# shift.net
KiCad netlist of a schematic drawn in Altium Designer
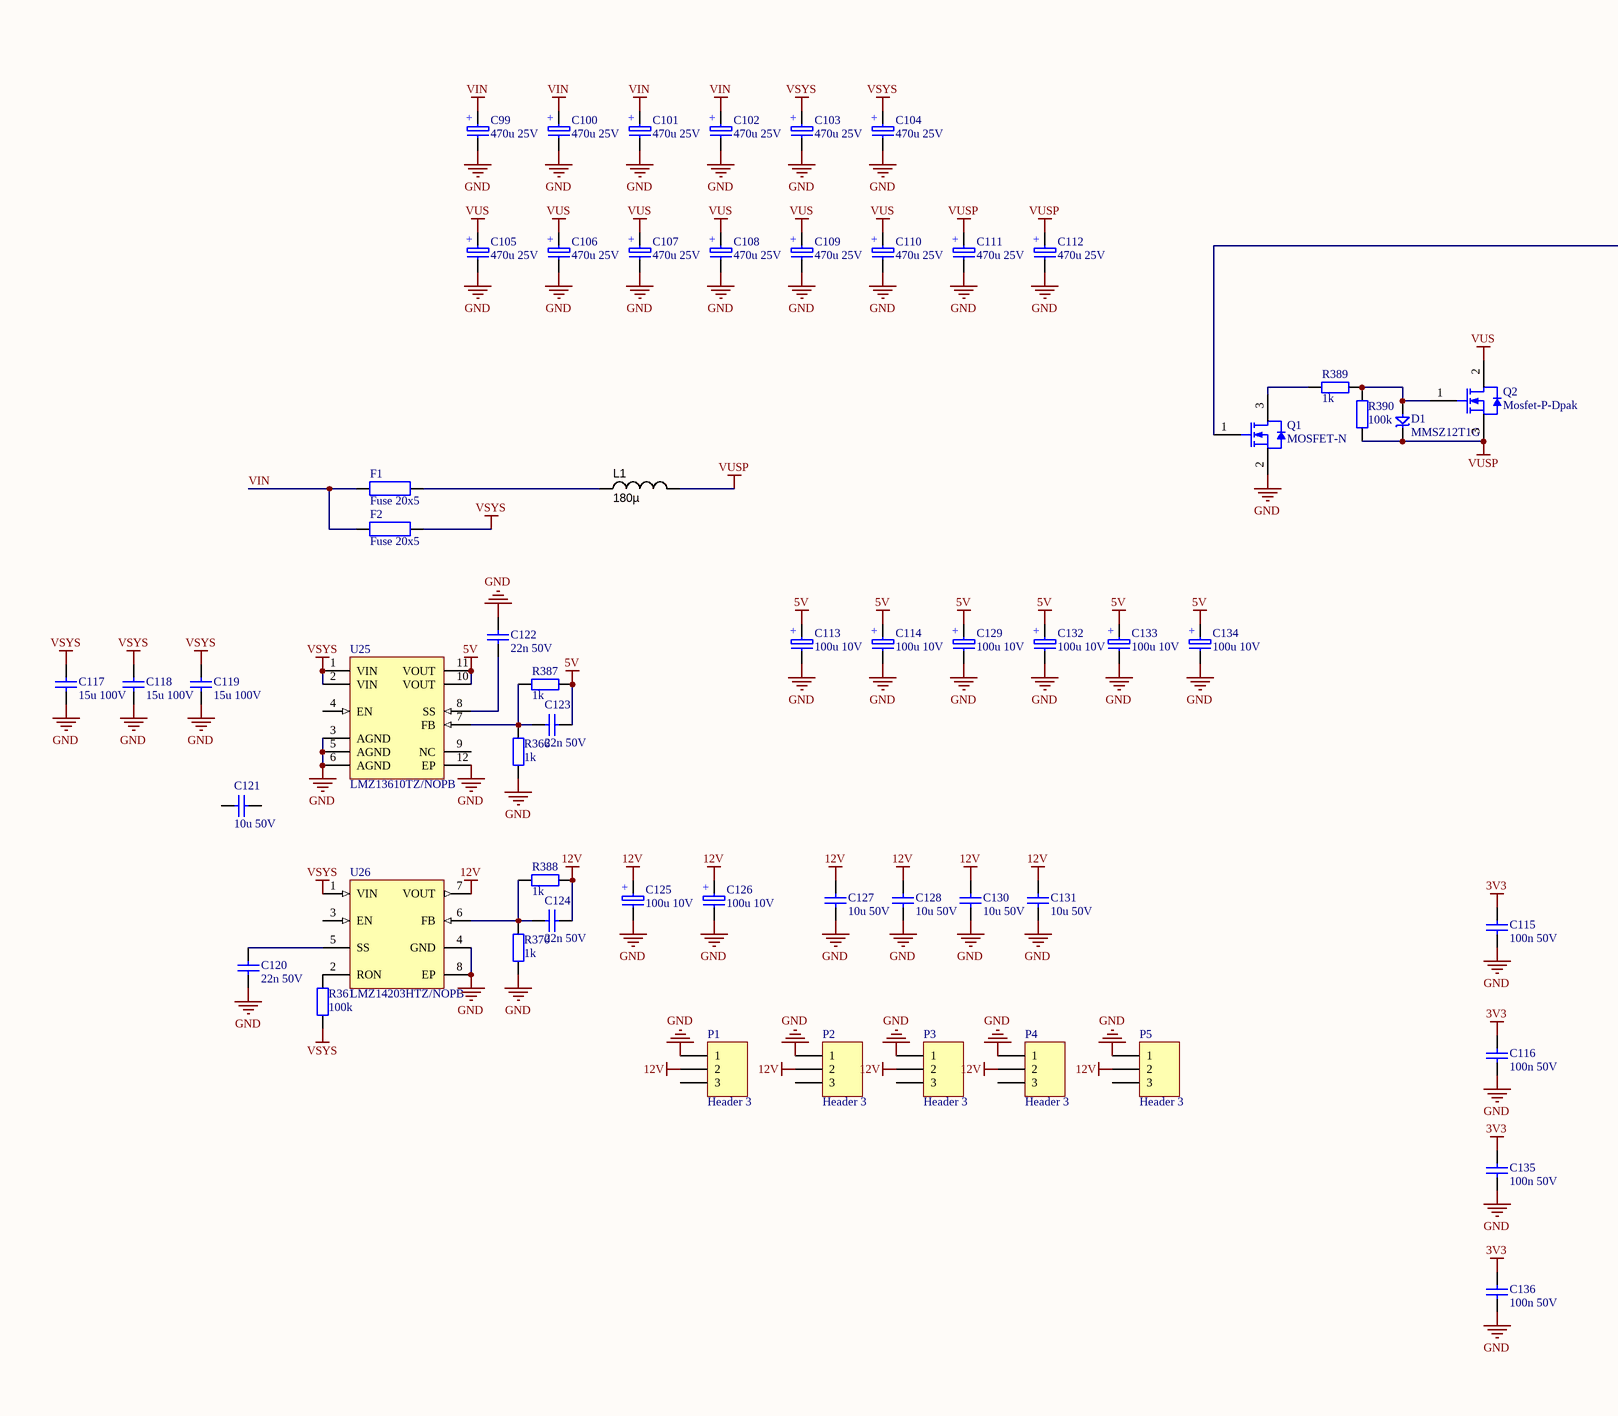
[diagram p0: shift.SchDoc, left]
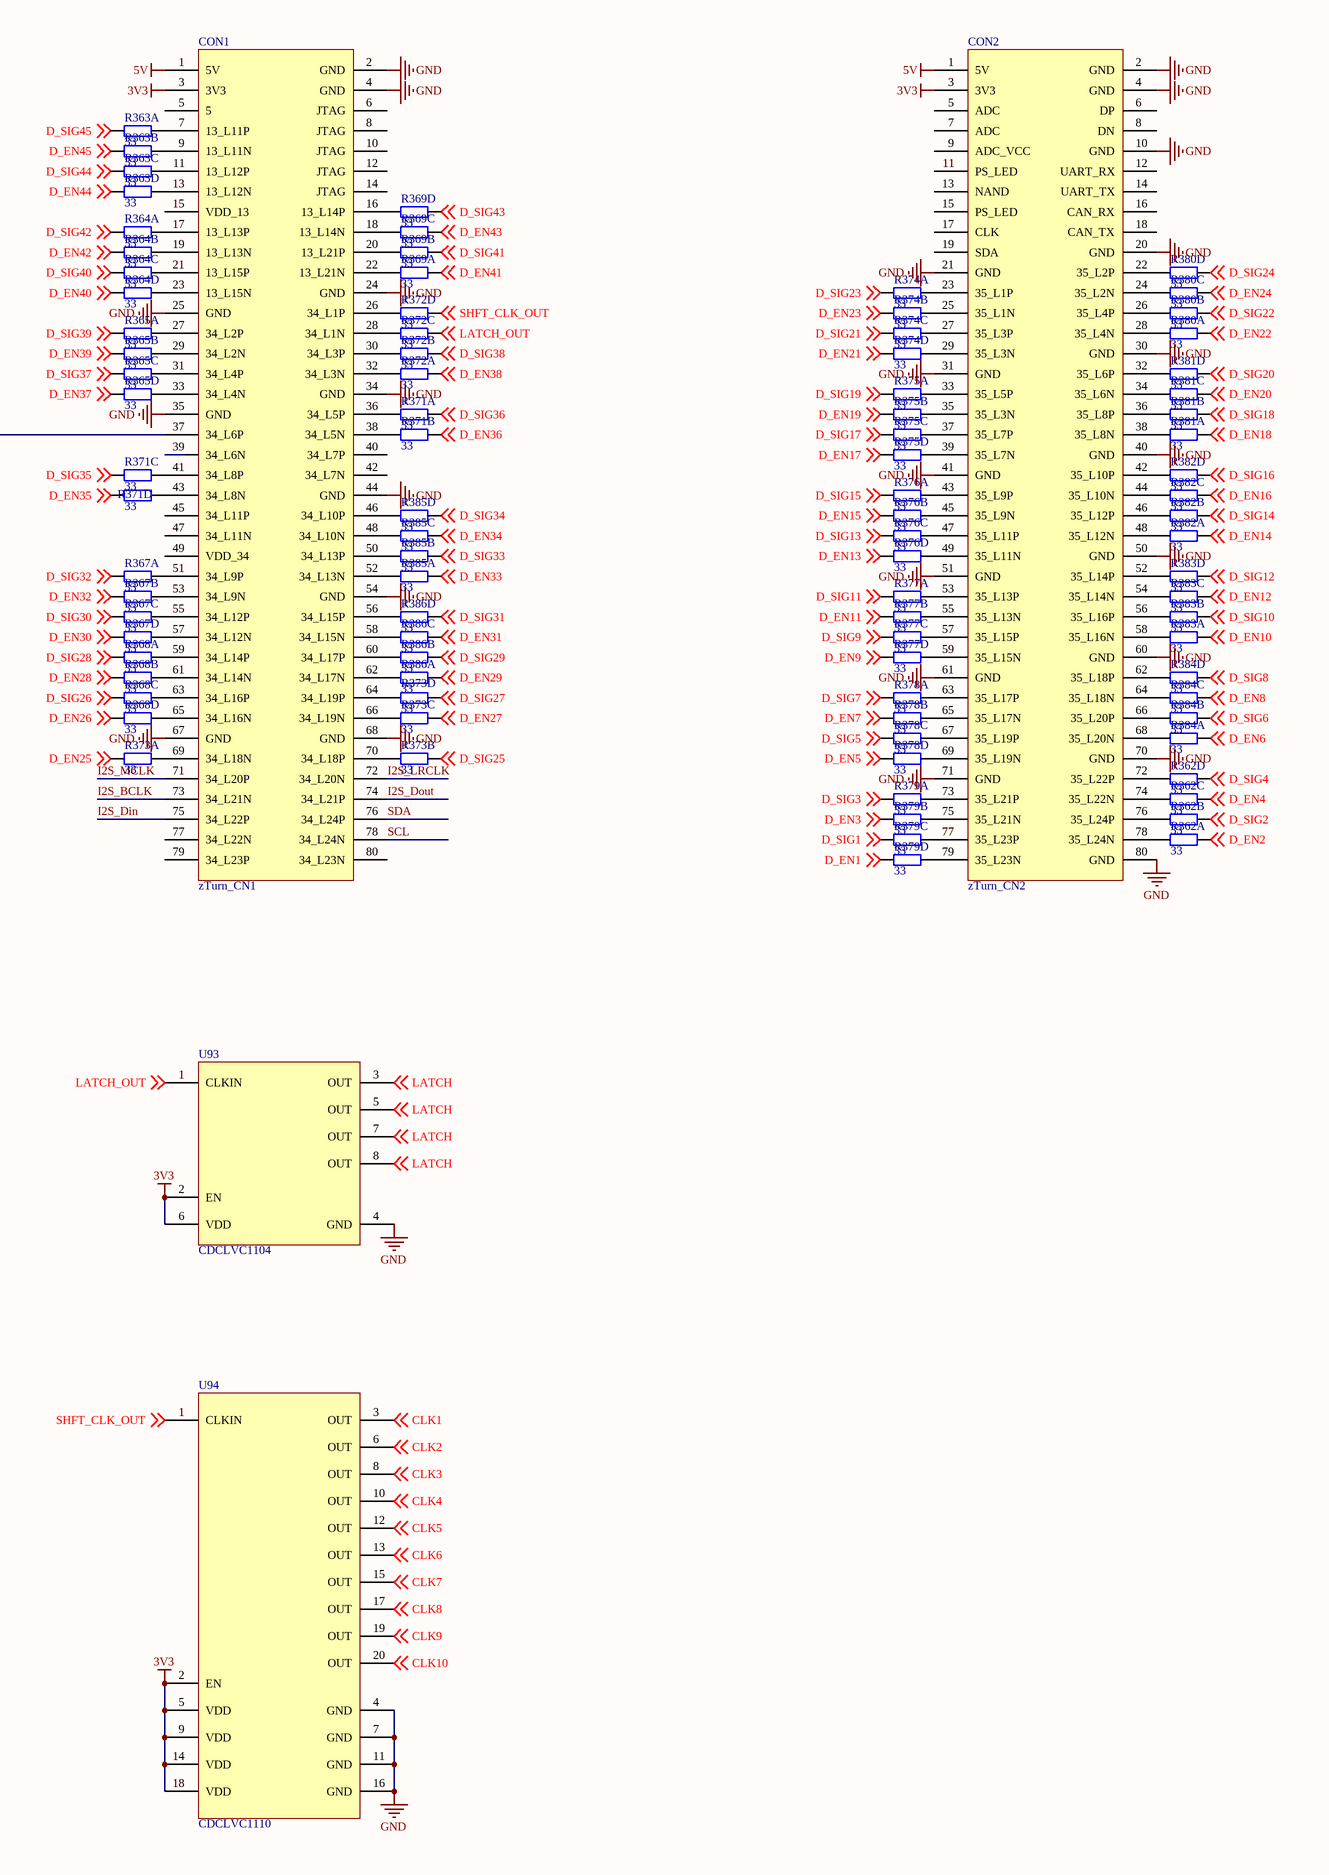
[diagram p1: shift.SchDoc, right]

(export (version "E")
  (design (tool "Eeschema 10.0.6"))
  (components
    (comp (ref "C99")
      (value "470u 25V")
      (footprint "SMD-10x10")
      (description "electrolytic capacitor 470u 25V")
      (libsource (lib "Passives") (part "CE-SMD-470u-25V"))
    )
    (comp (ref "C100")
      (value "470u 25V")
      (footprint "SMD-10x10")
      (description "electrolytic capacitor 470u 25V")
      (libsource (lib "Passives") (part "CE-SMD-470u-25V"))
    )
    (comp (ref "C101")
      (value "470u 25V")
      (footprint "SMD-10x10")
      (description "electrolytic capacitor 470u 25V")
      (libsource (lib "Passives") (part "CE-SMD-470u-25V"))
    )
    (comp (ref "C102")
      (value "470u 25V")
      (footprint "SMD-10x10")
      (description "electrolytic capacitor 470u 25V")
      (libsource (lib "Passives") (part "CE-SMD-470u-25V"))
    )
    (comp (ref "C103")
      (value "470u 25V")
      (footprint "SMD-10x10")
      (description "electrolytic capacitor 470u 25V")
      (libsource (lib "Passives") (part "CE-SMD-470u-25V"))
    )
    (comp (ref "C104")
      (value "470u 25V")
      (footprint "SMD-10x10")
      (description "electrolytic capacitor 470u 25V")
      (libsource (lib "Passives") (part "CE-SMD-470u-25V"))
    )
    (comp (ref "C105")
      (value "470u 25V")
      (footprint "SMD-10x10")
      (description "electrolytic capacitor 470u 25V")
      (libsource (lib "Passives") (part "CE-SMD-470u-25V"))
    )
    (comp (ref "C106")
      (value "470u 25V")
      (footprint "SMD-10x10")
      (description "electrolytic capacitor 470u 25V")
      (libsource (lib "Passives") (part "CE-SMD-470u-25V"))
    )
    (comp (ref "C107")
      (value "470u 25V")
      (footprint "SMD-10x10")
      (description "electrolytic capacitor 470u 25V")
      (libsource (lib "Passives") (part "CE-SMD-470u-25V"))
    )
    (comp (ref "C108")
      (value "470u 25V")
      (footprint "SMD-10x10")
      (description "electrolytic capacitor 470u 25V")
      (libsource (lib "Passives") (part "CE-SMD-470u-25V"))
    )
    (comp (ref "C109")
      (value "470u 25V")
      (footprint "SMD-10x10")
      (description "electrolytic capacitor 470u 25V")
      (libsource (lib "Passives") (part "CE-SMD-470u-25V"))
    )
    (comp (ref "C110")
      (value "470u 25V")
      (footprint "SMD-10x10")
      (description "electrolytic capacitor 470u 25V")
      (libsource (lib "Passives") (part "CE-SMD-470u-25V"))
    )
    (comp (ref "C111")
      (value "470u 25V")
      (footprint "SMD-10x10")
      (description "electrolytic capacitor 470u 25V")
      (libsource (lib "Passives") (part "CE-SMD-470u-25V"))
    )
    (comp (ref "C112")
      (value "470u 25V")
      (footprint "SMD-10x10")
      (description "electrolytic capacitor 470u 25V")
      (libsource (lib "Passives") (part "CE-SMD-470u-25V"))
    )
    (comp (ref "C113")
      (value "100u 10V")
      (footprint "C-TANT-C 2.8mm")
      (description "Capacitor Tantalum 100uF 10V")
      (libsource (lib "Passives") (part "C-TANT-100u-10V"))
    )
    (comp (ref "C114")
      (value "100u 10V")
      (footprint "C-TANT-C 2.8mm")
      (description "Capacitor Tantalum 100uF 10V")
      (libsource (lib "Passives") (part "C-TANT-100u-10V"))
    )
    (comp (ref "C115")
      (value "100n 50V")
      (footprint "C-0603-M")
      (description "Capacitor 100n 50V")
      (libsource (lib "Passives") (part "C-0603-100n-50V"))
    )
    (comp (ref "C116")
      (value "100n 50V")
      (footprint "C-0603-M")
      (description "Capacitor 100n 50V")
      (libsource (lib "Passives") (part "C-0603-100n-50V"))
    )
    (comp (ref "C117")
      (value "15u 100V")
      (footprint "C-2220")
      (description "Capacitor 15uF 100V")
      (libsource (lib "Passives") (part "C-2220-15u-100V"))
    )
    (comp (ref "C118")
      (value "15u 100V")
      (footprint "C-2220")
      (description "Capacitor 15uF 100V")
      (libsource (lib "Passives") (part "C-2220-15u-100V"))
    )
    (comp (ref "C119")
      (value "15u 100V")
      (footprint "C-2220")
      (description "Capacitor 15uF 100V")
      (libsource (lib "Passives") (part "C-2220-15u-100V"))
    )
    (comp (ref "C120")
      (value "22n 50V")
      (footprint "C-0603-H")
      (description "Capacitor 22nF 50V")
      (libsource (lib "Passives") (part "C-0603-22n-50V"))
    )
    (comp (ref "C121")
      (value "10u 50V")
      (footprint "C-1206-H")
      (description "Capacitor 10uF 50V")
      (libsource (lib "Passives") (part "C-1206-10u-50V"))
    )
    (comp (ref "C122")
      (value "22n 50V")
      (footprint "C-0603-H")
      (description "Capacitor 22nF 50V")
      (libsource (lib "Passives") (part "C-0603-22n-50V"))
    )
    (comp (ref "C123")
      (value "22n 50V")
      (footprint "C-0603-H")
      (description "Capacitor 22nF 50V")
      (libsource (lib "Passives") (part "C-0603-22n-50V"))
    )
    (comp (ref "C124")
      (value "22n 50V")
      (footprint "C-0603-H")
      (description "Capacitor 22nF 50V")
      (libsource (lib "Passives") (part "C-0603-22n-50V"))
    )
    (comp (ref "C125")
      (value "100u 10V")
      (footprint "C-TANT-C 2.8mm")
      (description "Capacitor Tantalum 100uF 10V")
      (libsource (lib "Passives") (part "C-TANT-100u-10V"))
    )
    (comp (ref "C126")
      (value "100u 10V")
      (footprint "C-TANT-C 2.8mm")
      (description "Capacitor Tantalum 100uF 10V")
      (libsource (lib "Passives") (part "C-TANT-100u-10V"))
    )
    (comp (ref "C127")
      (value "10u 50V")
      (footprint "C-1206-H")
      (description "Capacitor 10uF 50V")
      (libsource (lib "Passives") (part "C-1206-10u-50V"))
    )
    (comp (ref "C128")
      (value "10u 50V")
      (footprint "C-1206-H")
      (description "Capacitor 10uF 50V")
      (libsource (lib "Passives") (part "C-1206-10u-50V"))
    )
    (comp (ref "C129")
      (value "100u 10V")
      (footprint "C-TANT-C 2.8mm")
      (description "Capacitor Tantalum 100uF 10V")
      (libsource (lib "Passives") (part "C-TANT-100u-10V"))
    )
    (comp (ref "C130")
      (value "10u 50V")
      (footprint "C-1206-H")
      (description "Capacitor 10uF 50V")
      (libsource (lib "Passives") (part "C-1206-10u-50V"))
    )
    (comp (ref "C131")
      (value "10u 50V")
      (footprint "C-1206-H")
      (description "Capacitor 10uF 50V")
      (libsource (lib "Passives") (part "C-1206-10u-50V"))
    )
    (comp (ref "C132")
      (value "100u 10V")
      (footprint "C-TANT-C 2.8mm")
      (description "Capacitor Tantalum 100uF 10V")
      (libsource (lib "Passives") (part "C-TANT-100u-10V"))
    )
    (comp (ref "C133")
      (value "100u 10V")
      (footprint "C-TANT-C 2.8mm")
      (description "Capacitor Tantalum 100uF 10V")
      (libsource (lib "Passives") (part "C-TANT-100u-10V"))
    )
    (comp (ref "C134")
      (value "100u 10V")
      (footprint "C-TANT-C 2.8mm")
      (description "Capacitor Tantalum 100uF 10V")
      (libsource (lib "Passives") (part "C-TANT-100u-10V"))
    )
    (comp (ref "C135")
      (value "100n 50V")
      (footprint "C-0603-M")
      (description "Capacitor 100n 50V")
      (libsource (lib "Passives") (part "C-0603-100n-50V"))
    )
    (comp (ref "C136")
      (value "100n 50V")
      (footprint "C-0603-M")
      (description "Capacitor 100n 50V")
      (libsource (lib "Passives") (part "C-0603-100n-50V"))
    )
    (comp (ref "CON1")
      (value "zTurn_CN1")
      (footprint "zTurn")
      (libsource (lib "advanced") (part "zTurn_CN1"))
    )
    (comp (ref "CON2")
      (value "zTurn_CN2")
      (footprint "zTurn")
      (libsource (lib "advanced") (part "zTurn_CN2"))
    )
    (comp (ref "D1")
      (value "MMSZ12T1G")
      (footprint "SOD123")
      (libsource (lib "advanced") (part "Diode-Zener-12V"))
    )
    (comp (ref "F1")
      (value "Fuse 20x5")
      (footprint "FUSE-22.5")
      (libsource (lib "advanced") (part "FUSE-20x5"))
    )
    (comp (ref "F2")
      (value "Fuse 20x5")
      (footprint "FUSE-22.5")
      (libsource (lib "advanced") (part "FUSE-20x5"))
    )
    (comp (ref "L1")
      (value "180µ")
      (footprint "IND_SMD_TOROID_1.2x1.0in")
      (description "Power Inductor 180µH 10% SMD Toroid")
      (fields (field (name "TOLERANCE") "±10%") (field (name "Comment") "INDC_180u_Toroid"))
      (libsource (lib "PBL - Inductors") (part "INDC_180u_Toroid"))
    )
    (comp (ref "P1")
      (value "Header 3")
      (footprint "HDR1X3")
      (description "Header, 3-Pin")
      (fields (field (name "PUBLISHER") "Altium Limited"))
      (libsource (lib "Miscellaneous Connectors") (part "Header 3"))
    )
    (comp (ref "P2")
      (value "Header 3")
      (footprint "HDR1X3")
      (description "Header, 3-Pin")
      (fields (field (name "PUBLISHER") "Altium Limited"))
      (libsource (lib "Miscellaneous Connectors") (part "Header 3"))
    )
    (comp (ref "P3")
      (value "Header 3")
      (footprint "HDR1X3")
      (description "Header, 3-Pin")
      (fields (field (name "PUBLISHER") "Altium Limited"))
      (libsource (lib "Miscellaneous Connectors") (part "Header 3"))
    )
    (comp (ref "P4")
      (value "Header 3")
      (footprint "HDR1X3")
      (description "Header, 3-Pin")
      (fields (field (name "PUBLISHER") "Altium Limited"))
      (libsource (lib "Miscellaneous Connectors") (part "Header 3"))
    )
    (comp (ref "P5")
      (value "Header 3")
      (footprint "HDR1X3")
      (description "Header, 3-Pin")
      (fields (field (name "PUBLISHER") "Altium Limited"))
      (libsource (lib "Miscellaneous Connectors") (part "Header 3"))
    )
    (comp (ref "Q1") (value "MOSFET-N") (footprint "SOT-23") (libsource (lib "advanced") (part "MOSFET-N")))
    (comp (ref "Q2")
      (value "Mosfet-P-Dpak")
      (footprint "DPAK")
      (libsource (lib "advanced") (part "Mosfet-N-Dpak"))
    )
    (comp (ref "R361")
      (value "100k")
      (footprint "R-0603-H")
      (description "Resistor 100k")
      (libsource (lib "Passives") (part "R-0603-100k"))
    )
    (comp (ref "R362")
      (value "33")
      (footprint "CAC-50P200X100-8N")
      (description "Resistor Array 4x33")
      (libsource (lib "") (part "R-4x33_1"))
    )
    (comp (ref "R363")
      (value "33")
      (footprint "CAC-50P200X100-8N")
      (description "Resistor Array 4x33")
      (libsource (lib "Passives") (part "R-4x33"))
    )
    (comp (ref "R364")
      (value "33")
      (footprint "CAC-50P200X100-8N")
      (description "Resistor Array 4x33")
      (libsource (lib "Passives") (part "R-4x33"))
    )
    (comp (ref "R365")
      (value "33")
      (footprint "CAC-50P200X100-8N")
      (description "Resistor Array 4x33")
      (libsource (lib "Passives") (part "R-4x33"))
    )
    (comp (ref "R366")
      (value "1k")
      (footprint "R-0603-H")
      (description "Resistor 1k")
      (libsource (lib "") (part "R-0603-1k_1"))
    )
    (comp (ref "R367")
      (value "33")
      (footprint "CAC-50P200X100-8N")
      (description "Resistor Array 4x33")
      (libsource (lib "Passives") (part "R-4x33"))
    )
    (comp (ref "R368")
      (value "33")
      (footprint "CAC-50P200X100-8N")
      (description "Resistor Array 4x33")
      (libsource (lib "Passives") (part "R-4x33"))
    )
    (comp (ref "R369")
      (value "33")
      (footprint "CAC-50P200X100-8N")
      (description "Resistor Array 4x33")
      (libsource (lib "") (part "R-4x33_1"))
    )
    (comp (ref "R370")
      (value "1k")
      (footprint "R-0603-H")
      (description "Resistor 1k")
      (libsource (lib "") (part "R-0603-1k_1"))
    )
    (comp (ref "R371")
      (value "33")
      (footprint "CAC-50P200X100-8N")
      (description "Resistor Array 4x33")
      (libsource (lib "Passives") (part "R-4x33"))
    )
    (comp (ref "R372")
      (value "33")
      (footprint "CAC-50P200X100-8N")
      (description "Resistor Array 4x33")
      (libsource (lib "") (part "R-4x33_1"))
    )
    (comp (ref "R373")
      (value "33")
      (footprint "CAC-50P200X100-8N")
      (description "Resistor Array 4x33")
      (libsource (lib "Passives") (part "R-4x33"))
    )
    (comp (ref "R374")
      (value "33")
      (footprint "CAC-50P200X100-8N")
      (description "Resistor Array 4x33")
      (libsource (lib "Passives") (part "R-4x33"))
    )
    (comp (ref "R375")
      (value "33")
      (footprint "CAC-50P200X100-8N")
      (description "Resistor Array 4x33")
      (libsource (lib "Passives") (part "R-4x33"))
    )
    (comp (ref "R376")
      (value "33")
      (footprint "CAC-50P200X100-8N")
      (description "Resistor Array 4x33")
      (libsource (lib "Passives") (part "R-4x33"))
    )
    (comp (ref "R377")
      (value "33")
      (footprint "CAC-50P200X100-8N")
      (description "Resistor Array 4x33")
      (libsource (lib "Passives") (part "R-4x33"))
    )
    (comp (ref "R378")
      (value "33")
      (footprint "CAC-50P200X100-8N")
      (description "Resistor Array 4x33")
      (libsource (lib "Passives") (part "R-4x33"))
    )
    (comp (ref "R379")
      (value "33")
      (footprint "CAC-50P200X100-8N")
      (description "Resistor Array 4x33")
      (libsource (lib "Passives") (part "R-4x33"))
    )
    (comp (ref "R380")
      (value "33")
      (footprint "CAC-50P200X100-8N")
      (description "Resistor Array 4x33")
      (libsource (lib "") (part "R-4x33_1"))
    )
    (comp (ref "R381")
      (value "33")
      (footprint "CAC-50P200X100-8N")
      (description "Resistor Array 4x33")
      (libsource (lib "") (part "R-4x33_1"))
    )
    (comp (ref "R382")
      (value "33")
      (footprint "CAC-50P200X100-8N")
      (description "Resistor Array 4x33")
      (libsource (lib "") (part "R-4x33_1"))
    )
    (comp (ref "R383")
      (value "33")
      (footprint "CAC-50P200X100-8N")
      (description "Resistor Array 4x33")
      (libsource (lib "") (part "R-4x33_1"))
    )
    (comp (ref "R384")
      (value "33")
      (footprint "CAC-50P200X100-8N")
      (description "Resistor Array 4x33")
      (libsource (lib "") (part "R-4x33_1"))
    )
    (comp (ref "R385")
      (value "33")
      (footprint "CAC-50P200X100-8N")
      (description "Resistor Array 4x33")
      (libsource (lib "") (part "R-4x33_1"))
    )
    (comp (ref "R386")
      (value "33")
      (footprint "CAC-50P200X100-8N")
      (description "Resistor Array 4x33")
      (libsource (lib "") (part "R-4x33_1"))
    )
    (comp (ref "R387")
      (value "1k")
      (footprint "R-0603-H")
      (description "Resistor 1k")
      (libsource (lib "Passives") (part "R-0603-1k"))
    )
    (comp (ref "R388")
      (value "1k")
      (footprint "R-0603-H")
      (description "Resistor 1k")
      (libsource (lib "Passives") (part "R-0603-1k"))
    )
    (comp (ref "R389")
      (value "1k")
      (footprint "R-0603-H")
      (description "Resistor 1k")
      (libsource (lib "Passives") (part "R-0603-1k"))
    )
    (comp (ref "R390")
      (value "100k")
      (footprint "R-0603-H")
      (description "Resistor 100k")
      (libsource (lib "Passives") (part "R-0603-100k"))
    )
    (comp (ref "U25")
      (value "LMZ13610TZ/NOPB")
      (footprint "NDY0011A_M")
      (description "10A SIMPLE SWITCHER® Power Module with 36V Maximum Input Voltage, 11 pin TO-PMOD, 32 Rail")
      (fields (field (name "MANUFACTURER") "Texas Instruments"))
      (libsource (lib "Altium Content Vault") (part "PM-REG-LMZ13610-12"))
    )
    (comp (ref "U26")
      (value "LMZ14203HTZ/NOPB")
      (footprint "NDW0007A_V")
      (fields (field (name "MANUFACTURER") "Texas Instruments"))
      (libsource (lib "Altium Content Vault") (part "PM-REG-LMZ12003-8"))
    )
    (comp (ref "U93")
      (value "CDCLVC1104")
      (footprint "TSSOP65P640X120-8N")
      (libsource (lib "advanced") (part "CDCLVC1104"))
    )
    (comp (ref "U94")
      (value "CDCLVC1110")
      (footprint "TSSOP20")
      (libsource (lib "advanced") (part "CDCLVC1110"))
    )
  )
  (nets
    (net (code "1") (name "/I2S_BCLK") (class "Default")
      (node (ref "CON1") (pin "73") (pinfunction "34_L21N_73") (pintype "passive"))
    )
    (net (code "2") (name "/I2S_Din") (class "Default")
      (node (ref "CON1") (pin "75") (pinfunction "34_L22P_75") (pintype "passive"))
    )
    (net (code "3") (name "/I2S_Dout") (class "Default")
      (node (ref "CON1") (pin "74") (pinfunction "34_L21P_74") (pintype "passive"))
    )
    (net (code "4") (name "/I2S_LRCLK") (class "Default")
      (node (ref "CON1") (pin "72") (pinfunction "34_L20N_72") (pintype "passive"))
    )
    (net (code "5") (name "/I2S_MCLK") (class "Default")
      (node (ref "CON1") (pin "71") (pinfunction "34_L20P_71") (pintype "passive"))
    )
    (net (code "6") (name "/SCL") (class "Default")
      (node (ref "CON1") (pin "78") (pinfunction "34_L24N_78") (pintype "passive"))
    )
    (net (code "7") (name "/SDA") (class "Default")
      (node (ref "CON1") (pin "76") (pinfunction "34_L24P_76") (pintype "passive"))
    )
    (net (code "8") (name "3V3") (class "Default")
      (node (ref "C115") (pin "2") (pinfunction "2_2") (pintype "passive"))
      (node (ref "C116") (pin "2") (pinfunction "2_2") (pintype "passive"))
      (node (ref "C135") (pin "2") (pinfunction "2_2") (pintype "passive"))
      (node (ref "C136") (pin "2") (pinfunction "2_2") (pintype "passive"))
      (node (ref "CON1") (pin "3") (pinfunction "3V3_3") (pintype "passive"))
      (node (ref "CON2") (pin "3") (pinfunction "3V3_3") (pintype "passive"))
      (node (ref "U93") (pin "2") (pinfunction "EN_2") (pintype "passive"))
      (node (ref "U93") (pin "6") (pinfunction "VDD_6") (pintype "passive"))
      (node (ref "U94") (pin "14") (pinfunction "VDD_14") (pintype "passive"))
      (node (ref "U94") (pin "18") (pinfunction "VDD_18") (pintype "passive"))
      (node (ref "U94") (pin "2") (pinfunction "EN_2") (pintype "passive"))
      (node (ref "U94") (pin "5") (pinfunction "VDD_5") (pintype "passive"))
      (node (ref "U94") (pin "9") (pinfunction "VDD_9") (pintype "passive"))
    )
    (net (code "9") (name "5V") (class "Default")
      (node (ref "C113") (pin "2") (pinfunction "2_2") (pintype "passive"))
      (node (ref "C114") (pin "2") (pinfunction "2_2") (pintype "passive"))
      (node (ref "C123") (pin "2") (pinfunction "2_2") (pintype "passive"))
      (node (ref "C129") (pin "2") (pinfunction "2_2") (pintype "passive"))
      (node (ref "C132") (pin "2") (pinfunction "2_2") (pintype "passive"))
      (node (ref "C133") (pin "2") (pinfunction "2_2") (pintype "passive"))
      (node (ref "C134") (pin "2") (pinfunction "2_2") (pintype "passive"))
      (node (ref "CON1") (pin "1") (pinfunction "5V_1") (pintype "passive"))
      (node (ref "CON2") (pin "1") (pinfunction "5V_1") (pintype "passive"))
      (node (ref "R387") (pin "2") (pinfunction "2_2") (pintype "passive"))
      (node (ref "U25") (pin "10") (pinfunction "VOUT_10") (pintype "power_in"))
      (node (ref "U25") (pin "11") (pinfunction "VOUT_11") (pintype "power_in"))
    )
    (net (code "10") (name "12V") (class "Default")
      (node (ref "C124") (pin "2") (pinfunction "2_2") (pintype "passive"))
      (node (ref "C125") (pin "2") (pinfunction "2_2") (pintype "passive"))
      (node (ref "C126") (pin "2") (pinfunction "2_2") (pintype "passive"))
      (node (ref "C127") (pin "1") (pinfunction "1_1") (pintype "passive"))
      (node (ref "C128") (pin "1") (pinfunction "1_1") (pintype "passive"))
      (node (ref "C130") (pin "1") (pinfunction "1_1") (pintype "passive"))
      (node (ref "C131") (pin "1") (pinfunction "1_1") (pintype "passive"))
      (node (ref "P1") (pin "2") (pinfunction "2_2") (pintype "passive"))
      (node (ref "P2") (pin "2") (pinfunction "2_2") (pintype "passive"))
      (node (ref "P3") (pin "2") (pinfunction "2_2") (pintype "passive"))
      (node (ref "P4") (pin "2") (pinfunction "2_2") (pintype "passive"))
      (node (ref "P5") (pin "2") (pinfunction "2_2") (pintype "passive"))
      (node (ref "R388") (pin "2") (pinfunction "2_2") (pintype "passive"))
      (node (ref "U26") (pin "7") (pinfunction "VOUT_7") (pintype "output"))
    )
    (net (code "11") (name "CLK1") (class "Default")
      (node (ref "U94") (pin "3") (pinfunction "OUT_3") (pintype "passive"))
    )
    (net (code "12") (name "CLK2") (class "Default")
      (node (ref "U94") (pin "6") (pinfunction "OUT_6") (pintype "passive"))
    )
    (net (code "13") (name "CLK3") (class "Default")
      (node (ref "U94") (pin "8") (pinfunction "OUT_8") (pintype "passive"))
    )
    (net (code "14") (name "CLK4") (class "Default")
      (node (ref "U94") (pin "10") (pinfunction "OUT_10") (pintype "passive"))
    )
    (net (code "15") (name "CLK5") (class "Default")
      (node (ref "U94") (pin "12") (pinfunction "OUT_12") (pintype "passive"))
    )
    (net (code "16") (name "CLK6") (class "Default")
      (node (ref "U94") (pin "13") (pinfunction "OUT_13") (pintype "passive"))
    )
    (net (code "17") (name "CLK7") (class "Default")
      (node (ref "U94") (pin "15") (pinfunction "OUT_15") (pintype "passive"))
    )
    (net (code "18") (name "CLK8") (class "Default")
      (node (ref "U94") (pin "17") (pinfunction "OUT_17") (pintype "passive"))
    )
    (net (code "19") (name "CLK9") (class "Default")
      (node (ref "U94") (pin "19") (pinfunction "OUT_19") (pintype "passive"))
    )
    (net (code "20") (name "CLK10") (class "Default")
      (node (ref "U94") (pin "20") (pinfunction "OUT_20") (pintype "passive"))
    )
    (net (code "21") (name "D_EN1") (class "Default")
      (node (ref "R379") (pin "5") (pinfunction "5_5") (pintype "passive"))
    )
    (net (code "22") (name "D_EN2") (class "Default")
      (node (ref "R362") (pin "8") (pinfunction "8_8") (pintype "passive"))
    )
    (net (code "23") (name "D_EN3") (class "Default")
      (node (ref "R379") (pin "7") (pinfunction "7_7") (pintype "passive"))
    )
    (net (code "24") (name "D_EN4") (class "Default")
      (node (ref "R362") (pin "6") (pinfunction "6_6") (pintype "passive"))
    )
    (net (code "25") (name "D_EN5") (class "Default")
      (node (ref "R378") (pin "5") (pinfunction "5_5") (pintype "passive"))
    )
    (net (code "26") (name "D_EN6") (class "Default")
      (node (ref "R384") (pin "8") (pinfunction "8_8") (pintype "passive"))
    )
    (net (code "27") (name "D_EN7") (class "Default")
      (node (ref "R378") (pin "7") (pinfunction "7_7") (pintype "passive"))
    )
    (net (code "28") (name "D_EN8") (class "Default")
      (node (ref "R384") (pin "6") (pinfunction "6_6") (pintype "passive"))
    )
    (net (code "29") (name "D_EN9") (class "Default")
      (node (ref "R377") (pin "5") (pinfunction "5_5") (pintype "passive"))
    )
    (net (code "30") (name "D_EN10") (class "Default")
      (node (ref "R383") (pin "8") (pinfunction "8_8") (pintype "passive"))
    )
    (net (code "31") (name "D_EN11") (class "Default")
      (node (ref "R377") (pin "7") (pinfunction "7_7") (pintype "passive"))
    )
    (net (code "32") (name "D_EN12") (class "Default")
      (node (ref "R383") (pin "6") (pinfunction "6_6") (pintype "passive"))
    )
    (net (code "33") (name "D_EN13") (class "Default")
      (node (ref "R376") (pin "5") (pinfunction "5_5") (pintype "passive"))
    )
    (net (code "34") (name "D_EN14") (class "Default")
      (node (ref "R382") (pin "8") (pinfunction "8_8") (pintype "passive"))
    )
    (net (code "35") (name "D_EN15") (class "Default")
      (node (ref "R376") (pin "7") (pinfunction "7_7") (pintype "passive"))
    )
    (net (code "36") (name "D_EN16") (class "Default")
      (node (ref "R382") (pin "6") (pinfunction "6_6") (pintype "passive"))
    )
    (net (code "37") (name "D_EN17") (class "Default")
      (node (ref "R375") (pin "5") (pinfunction "5_5") (pintype "passive"))
    )
    (net (code "38") (name "D_EN18") (class "Default")
      (node (ref "R381") (pin "8") (pinfunction "8_8") (pintype "passive"))
    )
    (net (code "39") (name "D_EN19") (class "Default")
      (node (ref "R375") (pin "7") (pinfunction "7_7") (pintype "passive"))
    )
    (net (code "40") (name "D_EN20") (class "Default")
      (node (ref "R381") (pin "6") (pinfunction "6_6") (pintype "passive"))
    )
    (net (code "41") (name "D_EN21") (class "Default")
      (node (ref "R374") (pin "5") (pinfunction "5_5") (pintype "passive"))
    )
    (net (code "42") (name "D_EN22") (class "Default")
      (node (ref "R380") (pin "8") (pinfunction "8_8") (pintype "passive"))
    )
    (net (code "43") (name "D_EN23") (class "Default")
      (node (ref "R374") (pin "7") (pinfunction "7_7") (pintype "passive"))
    )
    (net (code "44") (name "D_EN24") (class "Default")
      (node (ref "R380") (pin "6") (pinfunction "6_6") (pintype "passive"))
    )
    (net (code "45") (name "D_EN25") (class "Default")
      (node (ref "R373") (pin "8") (pinfunction "8_8") (pintype "passive"))
    )
    (net (code "46") (name "D_EN26") (class "Default")
      (node (ref "R368") (pin "5") (pinfunction "5_5") (pintype "passive"))
    )
    (net (code "47") (name "D_EN27") (class "Default")
      (node (ref "R373") (pin "6") (pinfunction "6_6") (pintype "passive"))
    )
    (net (code "48") (name "D_EN28") (class "Default")
      (node (ref "R368") (pin "7") (pinfunction "7_7") (pintype "passive"))
    )
    (net (code "49") (name "D_EN29") (class "Default")
      (node (ref "R386") (pin "8") (pinfunction "8_8") (pintype "passive"))
    )
    (net (code "50") (name "D_EN30") (class "Default")
      (node (ref "R367") (pin "5") (pinfunction "5_5") (pintype "passive"))
    )
    (net (code "51") (name "D_EN31") (class "Default")
      (node (ref "R386") (pin "6") (pinfunction "6_6") (pintype "passive"))
    )
    (net (code "52") (name "D_EN32") (class "Default")
      (node (ref "R367") (pin "7") (pinfunction "7_7") (pintype "passive"))
    )
    (net (code "53") (name "D_EN33") (class "Default")
      (node (ref "R385") (pin "8") (pinfunction "8_8") (pintype "passive"))
    )
    (net (code "54") (name "D_EN34") (class "Default")
      (node (ref "R385") (pin "6") (pinfunction "6_6") (pintype "passive"))
    )
    (net (code "55") (name "D_EN35") (class "Default")
      (node (ref "R371") (pin "5") (pinfunction "5_5") (pintype "passive"))
    )
    (net (code "56") (name "D_EN36") (class "Default")
      (node (ref "R371") (pin "2") (pinfunction "2_2") (pintype "passive"))
    )
    (net (code "57") (name "D_EN37") (class "Default")
      (node (ref "R365") (pin "5") (pinfunction "5_5") (pintype "passive"))
    )
    (net (code "58") (name "D_EN38") (class "Default")
      (node (ref "R372") (pin "8") (pinfunction "8_8") (pintype "passive"))
    )
    (net (code "59") (name "D_EN39") (class "Default")
      (node (ref "R365") (pin "7") (pinfunction "7_7") (pintype "passive"))
    )
    (net (code "60") (name "D_EN40") (class "Default")
      (node (ref "R364") (pin "5") (pinfunction "5_5") (pintype "passive"))
    )
    (net (code "61") (name "D_EN41") (class "Default")
      (node (ref "R369") (pin "8") (pinfunction "8_8") (pintype "passive"))
    )
    (net (code "62") (name "D_EN42") (class "Default")
      (node (ref "R364") (pin "7") (pinfunction "7_7") (pintype "passive"))
    )
    (net (code "63") (name "D_EN43") (class "Default")
      (node (ref "R369") (pin "6") (pinfunction "6_6") (pintype "passive"))
    )
    (net (code "64") (name "D_EN44") (class "Default")
      (node (ref "R363") (pin "5") (pinfunction "5_5") (pintype "passive"))
    )
    (net (code "65") (name "D_EN45") (class "Default")
      (node (ref "R363") (pin "7") (pinfunction "7_7") (pintype "passive"))
    )
    (net (code "66") (name "D_SIG1") (class "Default")
      (node (ref "R379") (pin "6") (pinfunction "6_6") (pintype "passive"))
    )
    (net (code "67") (name "D_SIG2") (class "Default")
      (node (ref "R362") (pin "7") (pinfunction "7_7") (pintype "passive"))
    )
    (net (code "68") (name "D_SIG3") (class "Default")
      (node (ref "R379") (pin "8") (pinfunction "8_8") (pintype "passive"))
    )
    (net (code "69") (name "D_SIG4") (class "Default")
      (node (ref "R362") (pin "5") (pinfunction "5_5") (pintype "passive"))
    )
    (net (code "70") (name "D_SIG5") (class "Default")
      (node (ref "R378") (pin "6") (pinfunction "6_6") (pintype "passive"))
    )
    (net (code "71") (name "D_SIG6") (class "Default")
      (node (ref "R384") (pin "7") (pinfunction "7_7") (pintype "passive"))
    )
    (net (code "72") (name "D_SIG7") (class "Default")
      (node (ref "R378") (pin "8") (pinfunction "8_8") (pintype "passive"))
    )
    (net (code "73") (name "D_SIG8") (class "Default")
      (node (ref "R384") (pin "5") (pinfunction "5_5") (pintype "passive"))
    )
    (net (code "74") (name "D_SIG9") (class "Default")
      (node (ref "R377") (pin "6") (pinfunction "6_6") (pintype "passive"))
    )
    (net (code "75") (name "D_SIG10") (class "Default")
      (node (ref "R383") (pin "7") (pinfunction "7_7") (pintype "passive"))
    )
    (net (code "76") (name "D_SIG11") (class "Default")
      (node (ref "R377") (pin "8") (pinfunction "8_8") (pintype "passive"))
    )
    (net (code "77") (name "D_SIG12") (class "Default")
      (node (ref "R383") (pin "5") (pinfunction "5_5") (pintype "passive"))
    )
    (net (code "78") (name "D_SIG13") (class "Default")
      (node (ref "R376") (pin "6") (pinfunction "6_6") (pintype "passive"))
    )
    (net (code "79") (name "D_SIG14") (class "Default")
      (node (ref "R382") (pin "7") (pinfunction "7_7") (pintype "passive"))
    )
    (net (code "80") (name "D_SIG15") (class "Default")
      (node (ref "R376") (pin "8") (pinfunction "8_8") (pintype "passive"))
    )
    (net (code "81") (name "D_SIG16") (class "Default")
      (node (ref "R382") (pin "5") (pinfunction "5_5") (pintype "passive"))
    )
    (net (code "82") (name "D_SIG17") (class "Default")
      (node (ref "R375") (pin "6") (pinfunction "6_6") (pintype "passive"))
    )
    (net (code "83") (name "D_SIG18") (class "Default")
      (node (ref "R381") (pin "7") (pinfunction "7_7") (pintype "passive"))
    )
    (net (code "84") (name "D_SIG19") (class "Default")
      (node (ref "R375") (pin "8") (pinfunction "8_8") (pintype "passive"))
    )
    (net (code "85") (name "D_SIG20") (class "Default")
      (node (ref "R381") (pin "5") (pinfunction "5_5") (pintype "passive"))
    )
    (net (code "86") (name "D_SIG21") (class "Default")
      (node (ref "R374") (pin "6") (pinfunction "6_6") (pintype "passive"))
    )
    (net (code "87") (name "D_SIG22") (class "Default")
      (node (ref "R380") (pin "7") (pinfunction "7_7") (pintype "passive"))
    )
    (net (code "88") (name "D_SIG23") (class "Default")
      (node (ref "R374") (pin "8") (pinfunction "8_8") (pintype "passive"))
    )
    (net (code "89") (name "D_SIG24") (class "Default")
      (node (ref "R380") (pin "5") (pinfunction "5_5") (pintype "passive"))
    )
    (net (code "90") (name "D_SIG25") (class "Default")
      (node (ref "R373") (pin "7") (pinfunction "7_7") (pintype "passive"))
    )
    (net (code "91") (name "D_SIG26") (class "Default")
      (node (ref "R368") (pin "6") (pinfunction "6_6") (pintype "passive"))
    )
    (net (code "92") (name "D_SIG27") (class "Default")
      (node (ref "R373") (pin "5") (pinfunction "5_5") (pintype "passive"))
    )
    (net (code "93") (name "D_SIG28") (class "Default")
      (node (ref "R368") (pin "8") (pinfunction "8_8") (pintype "passive"))
    )
    (net (code "94") (name "D_SIG29") (class "Default")
      (node (ref "R386") (pin "7") (pinfunction "7_7") (pintype "passive"))
    )
    (net (code "95") (name "D_SIG30") (class "Default")
      (node (ref "R367") (pin "6") (pinfunction "6_6") (pintype "passive"))
    )
    (net (code "96") (name "D_SIG31") (class "Default")
      (node (ref "R386") (pin "5") (pinfunction "5_5") (pintype "passive"))
    )
    (net (code "97") (name "D_SIG32") (class "Default")
      (node (ref "R367") (pin "8") (pinfunction "8_8") (pintype "passive"))
    )
    (net (code "98") (name "D_SIG33") (class "Default")
      (node (ref "R385") (pin "7") (pinfunction "7_7") (pintype "passive"))
    )
    (net (code "99") (name "D_SIG34") (class "Default")
      (node (ref "R385") (pin "5") (pinfunction "5_5") (pintype "passive"))
    )
    (net (code "100") (name "D_SIG35") (class "Default")
      (node (ref "R371") (pin "6") (pinfunction "6_6") (pintype "passive"))
    )
    (net (code "101") (name "D_SIG36") (class "Default")
      (node (ref "R371") (pin "1") (pinfunction "1_1") (pintype "passive"))
    )
    (net (code "102") (name "D_SIG37") (class "Default")
      (node (ref "R365") (pin "6") (pinfunction "6_6") (pintype "passive"))
    )
    (net (code "103") (name "D_SIG38") (class "Default")
      (node (ref "R372") (pin "7") (pinfunction "7_7") (pintype "passive"))
    )
    (net (code "104") (name "D_SIG39") (class "Default")
      (node (ref "R365") (pin "8") (pinfunction "8_8") (pintype "passive"))
    )
    (net (code "105") (name "D_SIG40") (class "Default")
      (node (ref "R364") (pin "6") (pinfunction "6_6") (pintype "passive"))
    )
    (net (code "106") (name "D_SIG41") (class "Default")
      (node (ref "R369") (pin "7") (pinfunction "7_7") (pintype "passive"))
    )
    (net (code "107") (name "D_SIG42") (class "Default")
      (node (ref "R364") (pin "8") (pinfunction "8_8") (pintype "passive"))
    )
    (net (code "108") (name "D_SIG43") (class "Default")
      (node (ref "R369") (pin "5") (pinfunction "5_5") (pintype "passive"))
    )
    (net (code "109") (name "D_SIG44") (class "Default")
      (node (ref "R363") (pin "6") (pinfunction "6_6") (pintype "passive"))
    )
    (net (code "110") (name "D_SIG45") (class "Default")
      (node (ref "R363") (pin "8") (pinfunction "8_8") (pintype "passive"))
    )
    (net (code "111") (name "GND") (class "Default")
      (node (ref "C100") (pin "1") (pinfunction "1_1") (pintype "passive"))
      (node (ref "C101") (pin "1") (pinfunction "1_1") (pintype "passive"))
      (node (ref "C102") (pin "1") (pinfunction "1_1") (pintype "passive"))
      (node (ref "C103") (pin "1") (pinfunction "1_1") (pintype "passive"))
      (node (ref "C104") (pin "1") (pinfunction "1_1") (pintype "passive"))
      (node (ref "C105") (pin "1") (pinfunction "1_1") (pintype "passive"))
      (node (ref "C106") (pin "1") (pinfunction "1_1") (pintype "passive"))
      (node (ref "C107") (pin "1") (pinfunction "1_1") (pintype "passive"))
      (node (ref "C108") (pin "1") (pinfunction "1_1") (pintype "passive"))
      (node (ref "C109") (pin "1") (pinfunction "1_1") (pintype "passive"))
      (node (ref "C110") (pin "1") (pinfunction "1_1") (pintype "passive"))
      (node (ref "C111") (pin "1") (pinfunction "1_1") (pintype "passive"))
      (node (ref "C112") (pin "1") (pinfunction "1_1") (pintype "passive"))
      (node (ref "C113") (pin "1") (pinfunction "1_1") (pintype "passive"))
      (node (ref "C114") (pin "1") (pinfunction "1_1") (pintype "passive"))
      (node (ref "C115") (pin "1") (pinfunction "1_1") (pintype "passive"))
      (node (ref "C116") (pin "1") (pinfunction "1_1") (pintype "passive"))
      (node (ref "C117") (pin "1") (pinfunction "1_1") (pintype "passive"))
      (node (ref "C118") (pin "1") (pinfunction "1_1") (pintype "passive"))
      (node (ref "C119") (pin "1") (pinfunction "1_1") (pintype "passive"))
      (node (ref "C120") (pin "1") (pinfunction "1_1") (pintype "passive"))
      (node (ref "C122") (pin "1") (pinfunction "1_1") (pintype "passive"))
      (node (ref "C125") (pin "1") (pinfunction "1_1") (pintype "passive"))
      (node (ref "C126") (pin "1") (pinfunction "1_1") (pintype "passive"))
      (node (ref "C127") (pin "2") (pinfunction "2_2") (pintype "passive"))
      (node (ref "C128") (pin "2") (pinfunction "2_2") (pintype "passive"))
      (node (ref "C129") (pin "1") (pinfunction "1_1") (pintype "passive"))
      (node (ref "C130") (pin "2") (pinfunction "2_2") (pintype "passive"))
      (node (ref "C131") (pin "2") (pinfunction "2_2") (pintype "passive"))
      (node (ref "C132") (pin "1") (pinfunction "1_1") (pintype "passive"))
      (node (ref "C133") (pin "1") (pinfunction "1_1") (pintype "passive"))
      (node (ref "C134") (pin "1") (pinfunction "1_1") (pintype "passive"))
      (node (ref "C135") (pin "1") (pinfunction "1_1") (pintype "passive"))
      (node (ref "C136") (pin "1") (pinfunction "1_1") (pintype "passive"))
      (node (ref "C99") (pin "1") (pinfunction "1_1") (pintype "passive"))
      (node (ref "CON1") (pin "2") (pinfunction "GND_2") (pintype "passive"))
      (node (ref "CON1") (pin "24") (pinfunction "GND_24") (pintype "passive"))
      (node (ref "CON1") (pin "25") (pinfunction "GND_25") (pintype "passive"))
      (node (ref "CON1") (pin "34") (pinfunction "GND_34") (pintype "passive"))
      (node (ref "CON1") (pin "35") (pinfunction "GND_35") (pintype "passive"))
      (node (ref "CON1") (pin "4") (pinfunction "GND_4") (pintype "passive"))
      (node (ref "CON1") (pin "44") (pinfunction "GND_44") (pintype "passive"))
      (node (ref "CON1") (pin "54") (pinfunction "GND_54") (pintype "passive"))
      (node (ref "CON1") (pin "67") (pinfunction "GND_67") (pintype "passive"))
      (node (ref "CON1") (pin "68") (pinfunction "GND_68") (pintype "passive"))
      (node (ref "CON2") (pin "10") (pinfunction "GND_10") (pintype "passive"))
      (node (ref "CON2") (pin "2") (pinfunction "GND_2") (pintype "passive"))
      (node (ref "CON2") (pin "20") (pinfunction "GND_20") (pintype "passive"))
      (node (ref "CON2") (pin "21") (pinfunction "GND_21") (pintype "passive"))
      (node (ref "CON2") (pin "30") (pinfunction "GND_30") (pintype "passive"))
      (node (ref "CON2") (pin "31") (pinfunction "GND_31") (pintype "passive"))
      (node (ref "CON2") (pin "4") (pinfunction "GND_4") (pintype "passive"))
      (node (ref "CON2") (pin "40") (pinfunction "GND_40") (pintype "passive"))
      (node (ref "CON2") (pin "41") (pinfunction "GND_41") (pintype "passive"))
      (node (ref "CON2") (pin "50") (pinfunction "GND_50") (pintype "passive"))
      (node (ref "CON2") (pin "51") (pinfunction "GND_51") (pintype "passive"))
      (node (ref "CON2") (pin "60") (pinfunction "GND_60") (pintype "passive"))
      (node (ref "CON2") (pin "61") (pinfunction "GND_61") (pintype "passive"))
      (node (ref "CON2") (pin "70") (pinfunction "GND_70") (pintype "passive"))
      (node (ref "CON2") (pin "71") (pinfunction "GND_71") (pintype "passive"))
      (node (ref "CON2") (pin "80") (pinfunction "GND_80") (pintype "passive"))
      (node (ref "P1") (pin "1") (pinfunction "1_1") (pintype "passive"))
      (node (ref "P2") (pin "1") (pinfunction "1_1") (pintype "passive"))
      (node (ref "P3") (pin "1") (pinfunction "1_1") (pintype "passive"))
      (node (ref "P4") (pin "1") (pinfunction "1_1") (pintype "passive"))
      (node (ref "P5") (pin "1") (pinfunction "1_1") (pintype "passive"))
      (node (ref "Q1") (pin "2") (pintype "passive"))
      (node (ref "R366") (pin "1") (pinfunction "1_1") (pintype "passive"))
      (node (ref "R370") (pin "1") (pinfunction "1_1") (pintype "passive"))
      (node (ref "U25") (pin "12") (pinfunction "EP_12") (pintype "power_in"))
      (node (ref "U25") (pin "3") (pinfunction "AGND_3") (pintype "power_in"))
      (node (ref "U25") (pin "5") (pinfunction "AGND_5") (pintype "power_in"))
      (node (ref "U25") (pin "6") (pinfunction "AGND_6") (pintype "power_in"))
      (node (ref "U26") (pin "4") (pinfunction "GND_4") (pintype "power_in"))
      (node (ref "U26") (pin "8") (pinfunction "EP_8") (pintype "passive"))
      (node (ref "U93") (pin "4") (pinfunction "GND_4") (pintype "passive"))
      (node (ref "U94") (pin "11") (pinfunction "GND_11") (pintype "passive"))
      (node (ref "U94") (pin "16") (pinfunction "GND_16") (pintype "passive"))
      (node (ref "U94") (pin "4") (pinfunction "GND_4") (pintype "passive"))
      (node (ref "U94") (pin "7") (pinfunction "GND_7") (pintype "passive"))
    )
    (net (code "112") (name "LATCH") (class "Default")
      (node (ref "U93") (pin "3") (pinfunction "OUT_3") (pintype "passive"))
      (node (ref "U93") (pin "5") (pinfunction "OUT_5") (pintype "passive"))
      (node (ref "U93") (pin "7") (pinfunction "OUT_7") (pintype "passive"))
      (node (ref "U93") (pin "8") (pinfunction "OUT_8") (pintype "passive"))
    )
    (net (code "113") (name "LATCH_OUT") (class "Default")
      (node (ref "R372") (pin "6") (pinfunction "6_6") (pintype "passive"))
      (node (ref "U93") (pin "1") (pinfunction "CLKIN_1") (pintype "passive"))
    )
    (net (code "114") (name "Net-(CON1-13_L11N)") (class "Default")
      (node (ref "CON1") (pin "9") (pinfunction "13_L11N_9") (pintype "passive"))
      (node (ref "R363") (pin "2") (pinfunction "2_2") (pintype "passive"))
    )
    (net (code "115") (name "Net-(CON1-13_L11P)") (class "Default")
      (node (ref "CON1") (pin "7") (pinfunction "13_L11P_7") (pintype "passive"))
      (node (ref "R363") (pin "1") (pinfunction "1_1") (pintype "passive"))
    )
    (net (code "116") (name "Net-(CON1-13_L12N)") (class "Default")
      (node (ref "CON1") (pin "13") (pinfunction "13_L12N_13") (pintype "passive"))
      (node (ref "R363") (pin "4") (pinfunction "4_4") (pintype "passive"))
    )
    (net (code "117") (name "Net-(CON1-13_L12P)") (class "Default")
      (node (ref "CON1") (pin "11") (pinfunction "13_L12P_11") (pintype "passive"))
      (node (ref "R363") (pin "3") (pinfunction "3_3") (pintype "passive"))
    )
    (net (code "118") (name "Net-(CON1-13_L13N)") (class "Default")
      (node (ref "CON1") (pin "19") (pinfunction "13_L13N_19") (pintype "passive"))
      (node (ref "R364") (pin "2") (pinfunction "2_2") (pintype "passive"))
    )
    (net (code "119") (name "Net-(CON1-13_L13P)") (class "Default")
      (node (ref "CON1") (pin "17") (pinfunction "13_L13P_17") (pintype "passive"))
      (node (ref "R364") (pin "1") (pinfunction "1_1") (pintype "passive"))
    )
    (net (code "120") (name "Net-(CON1-13_L14N)") (class "Default")
      (node (ref "CON1") (pin "18") (pinfunction "13_L14N_18") (pintype "passive"))
      (node (ref "R369") (pin "3") (pinfunction "3_3") (pintype "passive"))
    )
    (net (code "121") (name "Net-(CON1-13_L14P)") (class "Default")
      (node (ref "CON1") (pin "16") (pinfunction "13_L14P_16") (pintype "passive"))
      (node (ref "R369") (pin "4") (pinfunction "4_4") (pintype "passive"))
    )
    (net (code "122") (name "Net-(CON1-13_L15N)") (class "Default")
      (node (ref "CON1") (pin "23") (pinfunction "13_L15N_23") (pintype "passive"))
      (node (ref "R364") (pin "4") (pinfunction "4_4") (pintype "passive"))
    )
    (net (code "123") (name "Net-(CON1-13_L15P)") (class "Default")
      (node (ref "CON1") (pin "21") (pinfunction "13_L15P_21") (pintype "passive"))
      (node (ref "R364") (pin "3") (pinfunction "3_3") (pintype "passive"))
    )
    (net (code "124") (name "Net-(CON1-13_L21N)") (class "Default")
      (node (ref "CON1") (pin "22") (pinfunction "13_L21N_22") (pintype "passive"))
      (node (ref "R369") (pin "1") (pinfunction "1_1") (pintype "passive"))
    )
    (net (code "125") (name "Net-(CON1-13_L21P)") (class "Default")
      (node (ref "CON1") (pin "20") (pinfunction "13_L21P_20") (pintype "passive"))
      (node (ref "R369") (pin "2") (pinfunction "2_2") (pintype "passive"))
    )
    (net (code "126") (name "Net-(CON1-34_L1N)") (class "Default")
      (node (ref "CON1") (pin "28") (pinfunction "34_L1N_28") (pintype "passive"))
      (node (ref "R372") (pin "3") (pinfunction "3_3") (pintype "passive"))
    )
    (net (code "127") (name "Net-(CON1-34_L1P)") (class "Default")
      (node (ref "CON1") (pin "26") (pinfunction "34_L1P_26") (pintype "passive"))
      (node (ref "R372") (pin "4") (pinfunction "4_4") (pintype "passive"))
    )
    (net (code "128") (name "Net-(CON1-34_L2N)") (class "Default")
      (node (ref "CON1") (pin "29") (pinfunction "34_L2N_29") (pintype "passive"))
      (node (ref "R365") (pin "2") (pinfunction "2_2") (pintype "passive"))
    )
    (net (code "129") (name "Net-(CON1-34_L2P)") (class "Default")
      (node (ref "CON1") (pin "27") (pinfunction "34_L2P_27") (pintype "passive"))
      (node (ref "R365") (pin "1") (pinfunction "1_1") (pintype "passive"))
    )
    (net (code "130") (name "Net-(CON1-34_L3N)") (class "Default")
      (node (ref "CON1") (pin "32") (pinfunction "34_L3N_32") (pintype "passive"))
      (node (ref "R372") (pin "1") (pinfunction "1_1") (pintype "passive"))
    )
    (net (code "131") (name "Net-(CON1-34_L3P)") (class "Default")
      (node (ref "CON1") (pin "30") (pinfunction "34_L3P_30") (pintype "passive"))
      (node (ref "R372") (pin "2") (pinfunction "2_2") (pintype "passive"))
    )
    (net (code "132") (name "Net-(CON1-34_L4N)") (class "Default")
      (node (ref "CON1") (pin "33") (pinfunction "34_L4N_33") (pintype "passive"))
      (node (ref "R365") (pin "4") (pinfunction "4_4") (pintype "passive"))
    )
    (net (code "133") (name "Net-(CON1-34_L4P)") (class "Default")
      (node (ref "CON1") (pin "31") (pinfunction "34_L4P_31") (pintype "passive"))
      (node (ref "R365") (pin "3") (pinfunction "3_3") (pintype "passive"))
    )
    (net (code "134") (name "Net-(CON1-34_L5N)") (class "Default")
      (node (ref "CON1") (pin "38") (pinfunction "34_L5N_38") (pintype "passive"))
      (node (ref "R371") (pin "7") (pinfunction "7_7") (pintype "passive"))
    )
    (net (code "135") (name "Net-(CON1-34_L5P)") (class "Default")
      (node (ref "CON1") (pin "36") (pinfunction "34_L5P_36") (pintype "passive"))
      (node (ref "R371") (pin "8") (pinfunction "8_8") (pintype "passive"))
    )
    (net (code "136") (name "Net-(CON1-34_L6P)") (class "Default")
      (node (ref "CON1") (pin "37") (pinfunction "34_L6P_37") (pintype "passive"))
      (node (ref "Q1") (pin "1") (pintype "passive"))
    )
    (net (code "137") (name "Net-(CON1-34_L8N)") (class "Default")
      (node (ref "CON1") (pin "43") (pinfunction "34_L8N_43") (pintype "passive"))
      (node (ref "R371") (pin "4") (pinfunction "4_4") (pintype "passive"))
    )
    (net (code "138") (name "Net-(CON1-34_L8P)") (class "Default")
      (node (ref "CON1") (pin "41") (pinfunction "34_L8P_41") (pintype "passive"))
      (node (ref "R371") (pin "3") (pinfunction "3_3") (pintype "passive"))
    )
    (net (code "139") (name "Net-(CON1-34_L9N)") (class "Default")
      (node (ref "CON1") (pin "53") (pinfunction "34_L9N_53") (pintype "passive"))
      (node (ref "R367") (pin "2") (pinfunction "2_2") (pintype "passive"))
    )
    (net (code "140") (name "Net-(CON1-34_L9P)") (class "Default")
      (node (ref "CON1") (pin "51") (pinfunction "34_L9P_51") (pintype "passive"))
      (node (ref "R367") (pin "1") (pinfunction "1_1") (pintype "passive"))
    )
    (net (code "141") (name "Net-(CON1-34_L10N)") (class "Default")
      (node (ref "CON1") (pin "48") (pinfunction "34_L10N_48") (pintype "passive"))
      (node (ref "R385") (pin "3") (pinfunction "3_3") (pintype "passive"))
    )
    (net (code "142") (name "Net-(CON1-34_L10P)") (class "Default")
      (node (ref "CON1") (pin "46") (pinfunction "34_L10P_46") (pintype "passive"))
      (node (ref "R385") (pin "4") (pinfunction "4_4") (pintype "passive"))
    )
    (net (code "143") (name "Net-(CON1-34_L12N)") (class "Default")
      (node (ref "CON1") (pin "57") (pinfunction "34_L12N_57") (pintype "passive"))
      (node (ref "R367") (pin "4") (pinfunction "4_4") (pintype "passive"))
    )
    (net (code "144") (name "Net-(CON1-34_L12P)") (class "Default")
      (node (ref "CON1") (pin "55") (pinfunction "34_L12P_55") (pintype "passive"))
      (node (ref "R367") (pin "3") (pinfunction "3_3") (pintype "passive"))
    )
    (net (code "145") (name "Net-(CON1-34_L13N)") (class "Default")
      (node (ref "CON1") (pin "52") (pinfunction "34_L13N_52") (pintype "passive"))
      (node (ref "R385") (pin "1") (pinfunction "1_1") (pintype "passive"))
    )
    (net (code "146") (name "Net-(CON1-34_L13P)") (class "Default")
      (node (ref "CON1") (pin "50") (pinfunction "34_L13P_50") (pintype "passive"))
      (node (ref "R385") (pin "2") (pinfunction "2_2") (pintype "passive"))
    )
    (net (code "147") (name "Net-(CON1-34_L14N)") (class "Default")
      (node (ref "CON1") (pin "61") (pinfunction "34_L14N_61") (pintype "passive"))
      (node (ref "R368") (pin "2") (pinfunction "2_2") (pintype "passive"))
    )
    (net (code "148") (name "Net-(CON1-34_L14P)") (class "Default")
      (node (ref "CON1") (pin "59") (pinfunction "34_L14P_59") (pintype "passive"))
      (node (ref "R368") (pin "1") (pinfunction "1_1") (pintype "passive"))
    )
    (net (code "149") (name "Net-(CON1-34_L15N)") (class "Default")
      (node (ref "CON1") (pin "58") (pinfunction "34_L15N_58") (pintype "passive"))
      (node (ref "R386") (pin "3") (pinfunction "3_3") (pintype "passive"))
    )
    (net (code "150") (name "Net-(CON1-34_L15P)") (class "Default")
      (node (ref "CON1") (pin "56") (pinfunction "34_L15P_56") (pintype "passive"))
      (node (ref "R386") (pin "4") (pinfunction "4_4") (pintype "passive"))
    )
    (net (code "151") (name "Net-(CON1-34_L16N)") (class "Default")
      (node (ref "CON1") (pin "65") (pinfunction "34_L16N_65") (pintype "passive"))
      (node (ref "R368") (pin "4") (pinfunction "4_4") (pintype "passive"))
    )
    (net (code "152") (name "Net-(CON1-34_L16P)") (class "Default")
      (node (ref "CON1") (pin "63") (pinfunction "34_L16P_63") (pintype "passive"))
      (node (ref "R368") (pin "3") (pinfunction "3_3") (pintype "passive"))
    )
    (net (code "153") (name "Net-(CON1-34_L17N)") (class "Default")
      (node (ref "CON1") (pin "62") (pinfunction "34_L17N_62") (pintype "passive"))
      (node (ref "R386") (pin "1") (pinfunction "1_1") (pintype "passive"))
    )
    (net (code "154") (name "Net-(CON1-34_L17P)") (class "Default")
      (node (ref "CON1") (pin "60") (pinfunction "34_L17P_60") (pintype "passive"))
      (node (ref "R386") (pin "2") (pinfunction "2_2") (pintype "passive"))
    )
    (net (code "155") (name "Net-(CON1-34_L18N)") (class "Default")
      (node (ref "CON1") (pin "69") (pinfunction "34_L18N_69") (pintype "passive"))
      (node (ref "R373") (pin "1") (pinfunction "1_1") (pintype "passive"))
    )
    (net (code "156") (name "Net-(CON1-34_L18P)") (class "Default")
      (node (ref "CON1") (pin "70") (pinfunction "34_L18P_70") (pintype "passive"))
      (node (ref "R373") (pin "2") (pinfunction "2_2") (pintype "passive"))
    )
    (net (code "157") (name "Net-(CON1-34_L19N)") (class "Default")
      (node (ref "CON1") (pin "66") (pinfunction "34_L19N_66") (pintype "passive"))
      (node (ref "R373") (pin "3") (pinfunction "3_3") (pintype "passive"))
    )
    (net (code "158") (name "Net-(CON1-34_L19P)") (class "Default")
      (node (ref "CON1") (pin "64") (pinfunction "34_L19P_64") (pintype "passive"))
      (node (ref "R373") (pin "4") (pinfunction "4_4") (pintype "passive"))
    )
    (net (code "159") (name "Net-(CON2-35_L1N)") (class "Default")
      (node (ref "CON2") (pin "25") (pinfunction "35_L1N_25") (pintype "passive"))
      (node (ref "R374") (pin "2") (pinfunction "2_2") (pintype "passive"))
    )
    (net (code "160") (name "Net-(CON2-35_L1P)") (class "Default")
      (node (ref "CON2") (pin "23") (pinfunction "35_L1P_23") (pintype "passive"))
      (node (ref "R374") (pin "1") (pinfunction "1_1") (pintype "passive"))
    )
    (net (code "161") (name "Net-(CON2-35_L2N)") (class "Default")
      (node (ref "CON2") (pin "24") (pinfunction "35_L2N_24") (pintype "passive"))
      (node (ref "R380") (pin "3") (pinfunction "3_3") (pintype "passive"))
    )
    (net (code "162") (name "Net-(CON2-35_L2P)") (class "Default")
      (node (ref "CON2") (pin "22") (pinfunction "35_L2P_22") (pintype "passive"))
      (node (ref "R380") (pin "4") (pinfunction "4_4") (pintype "passive"))
    )
    (net (code "163") (name "Net-(CON2-35_L3N-Pad29)") (class "Default")
      (node (ref "CON2") (pin "29") (pinfunction "35_L3N_29") (pintype "passive"))
      (node (ref "R374") (pin "4") (pinfunction "4_4") (pintype "passive"))
    )
    (net (code "164") (name "Net-(CON2-35_L3N-Pad35)") (class "Default")
      (node (ref "CON2") (pin "35") (pinfunction "35_L3N_35") (pintype "passive"))
      (node (ref "R375") (pin "2") (pinfunction "2_2") (pintype "passive"))
    )
    (net (code "165") (name "Net-(CON2-35_L3P)") (class "Default")
      (node (ref "CON2") (pin "27") (pinfunction "35_L3P_27") (pintype "passive"))
      (node (ref "R374") (pin "3") (pinfunction "3_3") (pintype "passive"))
    )
    (net (code "166") (name "Net-(CON2-35_L4N)") (class "Default")
      (node (ref "CON2") (pin "28") (pinfunction "35_L4N_28") (pintype "passive"))
      (node (ref "R380") (pin "1") (pinfunction "1_1") (pintype "passive"))
    )
    (net (code "167") (name "Net-(CON2-35_L4P)") (class "Default")
      (node (ref "CON2") (pin "26") (pinfunction "35_L4P_26") (pintype "passive"))
      (node (ref "R380") (pin "2") (pinfunction "2_2") (pintype "passive"))
    )
    (net (code "168") (name "Net-(CON2-35_L5P)") (class "Default")
      (node (ref "CON2") (pin "33") (pinfunction "35_L5P_33") (pintype "passive"))
      (node (ref "R375") (pin "1") (pinfunction "1_1") (pintype "passive"))
    )
    (net (code "169") (name "Net-(CON2-35_L6N)") (class "Default")
      (node (ref "CON2") (pin "34") (pinfunction "35_L6N_34") (pintype "passive"))
      (node (ref "R381") (pin "3") (pinfunction "3_3") (pintype "passive"))
    )
    (net (code "170") (name "Net-(CON2-35_L6P)") (class "Default")
      (node (ref "CON2") (pin "32") (pinfunction "35_L6P_32") (pintype "passive"))
      (node (ref "R381") (pin "4") (pinfunction "4_4") (pintype "passive"))
    )
    (net (code "171") (name "Net-(CON2-35_L7N)") (class "Default")
      (node (ref "CON2") (pin "39") (pinfunction "35_L7N_39") (pintype "passive"))
      (node (ref "R375") (pin "4") (pinfunction "4_4") (pintype "passive"))
    )
    (net (code "172") (name "Net-(CON2-35_L7P)") (class "Default")
      (node (ref "CON2") (pin "37") (pinfunction "35_L7P_37") (pintype "passive"))
      (node (ref "R375") (pin "3") (pinfunction "3_3") (pintype "passive"))
    )
    (net (code "173") (name "Net-(CON2-35_L8N)") (class "Default")
      (node (ref "CON2") (pin "38") (pinfunction "35_L8N_38") (pintype "passive"))
      (node (ref "R381") (pin "1") (pinfunction "1_1") (pintype "passive"))
    )
    (net (code "174") (name "Net-(CON2-35_L8P)") (class "Default")
      (node (ref "CON2") (pin "36") (pinfunction "35_L8P_36") (pintype "passive"))
      (node (ref "R381") (pin "2") (pinfunction "2_2") (pintype "passive"))
    )
    (net (code "175") (name "Net-(CON2-35_L9N)") (class "Default")
      (node (ref "CON2") (pin "45") (pinfunction "35_L9N_45") (pintype "passive"))
      (node (ref "R376") (pin "2") (pinfunction "2_2") (pintype "passive"))
    )
    (net (code "176") (name "Net-(CON2-35_L9P)") (class "Default")
      (node (ref "CON2") (pin "43") (pinfunction "35_L9P_43") (pintype "passive"))
      (node (ref "R376") (pin "1") (pinfunction "1_1") (pintype "passive"))
    )
    (net (code "177") (name "Net-(CON2-35_L10N)") (class "Default")
      (node (ref "CON2") (pin "44") (pinfunction "35_L10N_44") (pintype "passive"))
      (node (ref "R382") (pin "3") (pinfunction "3_3") (pintype "passive"))
    )
    (net (code "178") (name "Net-(CON2-35_L10P)") (class "Default")
      (node (ref "CON2") (pin "42") (pinfunction "35_L10P_42") (pintype "passive"))
      (node (ref "R382") (pin "4") (pinfunction "4_4") (pintype "passive"))
    )
    (net (code "179") (name "Net-(CON2-35_L11N)") (class "Default")
      (node (ref "CON2") (pin "49") (pinfunction "35_L11N_49") (pintype "passive"))
      (node (ref "R376") (pin "4") (pinfunction "4_4") (pintype "passive"))
    )
    (net (code "180") (name "Net-(CON2-35_L11P)") (class "Default")
      (node (ref "CON2") (pin "47") (pinfunction "35_L11P_47") (pintype "passive"))
      (node (ref "R376") (pin "3") (pinfunction "3_3") (pintype "passive"))
    )
    (net (code "181") (name "Net-(CON2-35_L12N)") (class "Default")
      (node (ref "CON2") (pin "48") (pinfunction "35_L12N_48") (pintype "passive"))
      (node (ref "R382") (pin "1") (pinfunction "1_1") (pintype "passive"))
    )
    (net (code "182") (name "Net-(CON2-35_L12P)") (class "Default")
      (node (ref "CON2") (pin "46") (pinfunction "35_L12P_46") (pintype "passive"))
      (node (ref "R382") (pin "2") (pinfunction "2_2") (pintype "passive"))
    )
    (net (code "183") (name "Net-(CON2-35_L13N)") (class "Default")
      (node (ref "CON2") (pin "55") (pinfunction "35_L13N_55") (pintype "passive"))
      (node (ref "R377") (pin "2") (pinfunction "2_2") (pintype "passive"))
    )
    (net (code "184") (name "Net-(CON2-35_L13P)") (class "Default")
      (node (ref "CON2") (pin "53") (pinfunction "35_L13P_53") (pintype "passive"))
      (node (ref "R377") (pin "1") (pinfunction "1_1") (pintype "passive"))
    )
    (net (code "185") (name "Net-(CON2-35_L14N)") (class "Default")
      (node (ref "CON2") (pin "54") (pinfunction "35_L14N_54") (pintype "passive"))
      (node (ref "R383") (pin "3") (pinfunction "3_3") (pintype "passive"))
    )
    (net (code "186") (name "Net-(CON2-35_L14P)") (class "Default")
      (node (ref "CON2") (pin "52") (pinfunction "35_L14P_52") (pintype "passive"))
      (node (ref "R383") (pin "4") (pinfunction "4_4") (pintype "passive"))
    )
    (net (code "187") (name "Net-(CON2-35_L15N)") (class "Default")
      (node (ref "CON2") (pin "59") (pinfunction "35_L15N_59") (pintype "passive"))
      (node (ref "R377") (pin "4") (pinfunction "4_4") (pintype "passive"))
    )
    (net (code "188") (name "Net-(CON2-35_L15P)") (class "Default")
      (node (ref "CON2") (pin "57") (pinfunction "35_L15P_57") (pintype "passive"))
      (node (ref "R377") (pin "3") (pinfunction "3_3") (pintype "passive"))
    )
    (net (code "189") (name "Net-(CON2-35_L16N)") (class "Default")
      (node (ref "CON2") (pin "58") (pinfunction "35_L16N_58") (pintype "passive"))
      (node (ref "R383") (pin "1") (pinfunction "1_1") (pintype "passive"))
    )
    (net (code "190") (name "Net-(CON2-35_L16P)") (class "Default")
      (node (ref "CON2") (pin "56") (pinfunction "35_L16P_56") (pintype "passive"))
      (node (ref "R383") (pin "2") (pinfunction "2_2") (pintype "passive"))
    )
    (net (code "191") (name "Net-(CON2-35_L17N)") (class "Default")
      (node (ref "CON2") (pin "65") (pinfunction "35_L17N_65") (pintype "passive"))
      (node (ref "R378") (pin "2") (pinfunction "2_2") (pintype "passive"))
    )
    (net (code "192") (name "Net-(CON2-35_L17P)") (class "Default")
      (node (ref "CON2") (pin "63") (pinfunction "35_L17P_63") (pintype "passive"))
      (node (ref "R378") (pin "1") (pinfunction "1_1") (pintype "passive"))
    )
    (net (code "193") (name "Net-(CON2-35_L18N)") (class "Default")
      (node (ref "CON2") (pin "64") (pinfunction "35_L18N_64") (pintype "passive"))
      (node (ref "R384") (pin "3") (pinfunction "3_3") (pintype "passive"))
    )
    (net (code "194") (name "Net-(CON2-35_L18P)") (class "Default")
      (node (ref "CON2") (pin "62") (pinfunction "35_L18P_62") (pintype "passive"))
      (node (ref "R384") (pin "4") (pinfunction "4_4") (pintype "passive"))
    )
    (net (code "195") (name "Net-(CON2-35_L19N)") (class "Default")
      (node (ref "CON2") (pin "69") (pinfunction "35_L19N_69") (pintype "passive"))
      (node (ref "R378") (pin "4") (pinfunction "4_4") (pintype "passive"))
    )
    (net (code "196") (name "Net-(CON2-35_L19P)") (class "Default")
      (node (ref "CON2") (pin "67") (pinfunction "35_L19P_67") (pintype "passive"))
      (node (ref "R378") (pin "3") (pinfunction "3_3") (pintype "passive"))
    )
    (net (code "197") (name "Net-(CON2-35_L20N)") (class "Default")
      (node (ref "CON2") (pin "68") (pinfunction "35_L20N_68") (pintype "passive"))
      (node (ref "R384") (pin "1") (pinfunction "1_1") (pintype "passive"))
    )
    (net (code "198") (name "Net-(CON2-35_L20P)") (class "Default")
      (node (ref "CON2") (pin "66") (pinfunction "35_L20P_66") (pintype "passive"))
      (node (ref "R384") (pin "2") (pinfunction "2_2") (pintype "passive"))
    )
    (net (code "199") (name "Net-(CON2-35_L21N)") (class "Default")
      (node (ref "CON2") (pin "75") (pinfunction "35_L21N_75") (pintype "passive"))
      (node (ref "R379") (pin "2") (pinfunction "2_2") (pintype "passive"))
    )
    (net (code "200") (name "Net-(CON2-35_L21P)") (class "Default")
      (node (ref "CON2") (pin "73") (pinfunction "35_L21P_73") (pintype "passive"))
      (node (ref "R379") (pin "1") (pinfunction "1_1") (pintype "passive"))
    )
    (net (code "201") (name "Net-(CON2-35_L22N)") (class "Default")
      (node (ref "CON2") (pin "74") (pinfunction "35_L22N_74") (pintype "passive"))
      (node (ref "R362") (pin "3") (pinfunction "3_3") (pintype "passive"))
    )
    (net (code "202") (name "Net-(CON2-35_L22P)") (class "Default")
      (node (ref "CON2") (pin "72") (pinfunction "35_L22P_72") (pintype "passive"))
      (node (ref "R362") (pin "4") (pinfunction "4_4") (pintype "passive"))
    )
    (net (code "203") (name "Net-(CON2-35_L23N)") (class "Default")
      (node (ref "CON2") (pin "79") (pinfunction "35_L23N_79") (pintype "passive"))
      (node (ref "R379") (pin "4") (pinfunction "4_4") (pintype "passive"))
    )
    (net (code "204") (name "Net-(CON2-35_L23P)") (class "Default")
      (node (ref "CON2") (pin "77") (pinfunction "35_L23P_77") (pintype "passive"))
      (node (ref "R379") (pin "3") (pinfunction "3_3") (pintype "passive"))
    )
    (net (code "205") (name "Net-(CON2-35_L24N)") (class "Default")
      (node (ref "CON2") (pin "78") (pinfunction "35_L24N_78") (pintype "passive"))
      (node (ref "R362") (pin "1") (pinfunction "1_1") (pintype "passive"))
    )
    (net (code "206") (name "Net-(CON2-35_L24P)") (class "Default")
      (node (ref "CON2") (pin "76") (pinfunction "35_L24P_76") (pintype "passive"))
      (node (ref "R362") (pin "2") (pinfunction "2_2") (pintype "passive"))
    )
    (net (code "207") (name "Net-(D1-an)") (class "Default")
      (node (ref "D1") (pin "1") (pinfunction "an_1") (pintype "passive"))
      (node (ref "Q2") (pin "1") (pintype "passive"))
      (node (ref "R389") (pin "2") (pinfunction "2_2") (pintype "passive"))
      (node (ref "R390") (pin "2") (pinfunction "2_2") (pintype "passive"))
    )
    (net (code "208") (name "Net-(F1-V+-Pad2)") (class "Default")
      (node (ref "F1") (pin "2") (pinfunction "V+_2") (pintype "passive"))
      (node (ref "L1") (pin "1") (pinfunction "1_1") (pintype "passive"))
    )
    (net (code "209") (name "Net-(Q1-Pad3)") (class "Default")
      (node (ref "Q1") (pin "3") (pintype "passive"))
      (node (ref "R389") (pin "1") (pinfunction "1_1") (pintype "passive"))
    )
    (net (code "210") (name "Net-(U25-FB)") (class "Default")
      (node (ref "C123") (pin "1") (pinfunction "1_1") (pintype "passive"))
      (node (ref "R366") (pin "2") (pinfunction "2_2") (pintype "passive"))
      (node (ref "R387") (pin "1") (pinfunction "1_1") (pintype "passive"))
      (node (ref "U25") (pin "7") (pinfunction "FB_7") (pintype "input"))
    )
    (net (code "211") (name "Net-(U25-SS)") (class "Default")
      (node (ref "C122") (pin "2") (pinfunction "2_2") (pintype "passive"))
      (node (ref "U25") (pin "8") (pinfunction "SS_8") (pintype "input"))
    )
    (net (code "212") (name "Net-(U26-FB)") (class "Default")
      (node (ref "C124") (pin "1") (pinfunction "1_1") (pintype "passive"))
      (node (ref "R370") (pin "2") (pinfunction "2_2") (pintype "passive"))
      (node (ref "R388") (pin "1") (pinfunction "1_1") (pintype "passive"))
      (node (ref "U26") (pin "6") (pinfunction "FB_6") (pintype "input"))
    )
    (net (code "213") (name "Net-(U26-RON)") (class "Default")
      (node (ref "R361") (pin "2") (pinfunction "2_2") (pintype "passive"))
      (node (ref "U26") (pin "2") (pinfunction "RON_2") (pintype "passive"))
    )
    (net (code "214") (name "Net-(U26-SS)") (class "Default")
      (node (ref "C120") (pin "2") (pinfunction "2_2") (pintype "passive"))
      (node (ref "U26") (pin "5") (pinfunction "SS_5") (pintype "passive"))
    )
    (net (code "215") (name "SHFT_CLK_OUT") (class "Default")
      (node (ref "R372") (pin "5") (pinfunction "5_5") (pintype "passive"))
      (node (ref "U94") (pin "1") (pinfunction "CLKIN_1") (pintype "passive"))
    )
    (net (code "216") (name "VIN") (class "Default")
      (node (ref "C100") (pin "2") (pinfunction "2_2") (pintype "passive"))
      (node (ref "C101") (pin "2") (pinfunction "2_2") (pintype "passive"))
      (node (ref "C102") (pin "2") (pinfunction "2_2") (pintype "passive"))
      (node (ref "C99") (pin "2") (pinfunction "2_2") (pintype "passive"))
      (node (ref "F1") (pin "1") (pinfunction "V+_1") (pintype "passive"))
      (node (ref "F2") (pin "1") (pinfunction "V+_1") (pintype "passive"))
    )
    (net (code "217") (name "VSYS") (class "Default")
      (node (ref "C103") (pin "2") (pinfunction "2_2") (pintype "passive"))
      (node (ref "C104") (pin "2") (pinfunction "2_2") (pintype "passive"))
      (node (ref "C117") (pin "2") (pinfunction "2_2") (pintype "passive"))
      (node (ref "C118") (pin "2") (pinfunction "2_2") (pintype "passive"))
      (node (ref "C119") (pin "2") (pinfunction "2_2") (pintype "passive"))
      (node (ref "F2") (pin "2") (pinfunction "V+_2") (pintype "passive"))
      (node (ref "R361") (pin "1") (pinfunction "1_1") (pintype "passive"))
      (node (ref "U25") (pin "1") (pinfunction "VIN_1") (pintype "power_in"))
      (node (ref "U25") (pin "2") (pinfunction "VIN_2") (pintype "power_in"))
      (node (ref "U26") (pin "1") (pinfunction "VIN_1") (pintype "input"))
    )
    (net (code "218") (name "VUS") (class "Default")
      (node (ref "C105") (pin "2") (pinfunction "2_2") (pintype "passive"))
      (node (ref "C106") (pin "2") (pinfunction "2_2") (pintype "passive"))
      (node (ref "C107") (pin "2") (pinfunction "2_2") (pintype "passive"))
      (node (ref "C108") (pin "2") (pinfunction "2_2") (pintype "passive"))
      (node (ref "C109") (pin "2") (pinfunction "2_2") (pintype "passive"))
      (node (ref "C110") (pin "2") (pinfunction "2_2") (pintype "passive"))
      (node (ref "Q2") (pin "2") (pintype "passive"))
    )
    (net (code "219") (name "VUSP") (class "Default")
      (node (ref "C111") (pin "2") (pinfunction "2_2") (pintype "passive"))
      (node (ref "C112") (pin "2") (pinfunction "2_2") (pintype "passive"))
      (node (ref "D1") (pin "2") (pinfunction "kt_2") (pintype "passive"))
      (node (ref "L1") (pin "2") (pinfunction "2_2") (pintype "passive"))
      (node (ref "Q2") (pin "3") (pintype "passive"))
      (node (ref "R390") (pin "1") (pinfunction "1_1") (pintype "passive"))
    )
    (net (code "220") (name "unconnected-(C121-Pad1)") (class "Default")
      (node (ref "C121") (pin "1") (pinfunction "1_1") (pintype "passive"))
    )
    (net (code "221") (name "unconnected-(C121-Pad2)") (class "Default")
      (node (ref "C121") (pin "2") (pinfunction "2_2") (pintype "passive"))
    )
    (net (code "222") (name "unconnected-(CON1-34_L6N-Pad39)") (class "Default")
      (node (ref "CON1") (pin "39") (pinfunction "34_L6N_39") (pintype "passive"))
    )
    (net (code "223") (name "unconnected-(CON1-34_L7N-Pad42)") (class "Default")
      (node (ref "CON1") (pin "42") (pinfunction "34_L7N_42") (pintype "passive"))
    )
    (net (code "224") (name "unconnected-(CON1-34_L7P-Pad40)") (class "Default")
      (node (ref "CON1") (pin "40") (pinfunction "34_L7P_40") (pintype "passive"))
    )
    (net (code "225") (name "unconnected-(CON1-34_L11N-Pad47)") (class "Default")
      (node (ref "CON1") (pin "47") (pinfunction "34_L11N_47") (pintype "passive"))
    )
    (net (code "226") (name "unconnected-(CON1-34_L11P-Pad45)") (class "Default")
      (node (ref "CON1") (pin "45") (pinfunction "34_L11P_45") (pintype "passive"))
    )
    (net (code "227") (name "unconnected-(CON1-34_L22N-Pad77)") (class "Default")
      (node (ref "CON1") (pin "77") (pinfunction "34_L22N_77") (pintype "passive"))
    )
    (net (code "228") (name "unconnected-(CON1-34_L23N-Pad80)") (class "Default")
      (node (ref "CON1") (pin "80") (pinfunction "34_L23N_80") (pintype "passive"))
    )
    (net (code "229") (name "unconnected-(CON1-34_L23P-Pad79)") (class "Default")
      (node (ref "CON1") (pin "79") (pinfunction "34_L23P_79") (pintype "passive"))
    )
    (net (code "230") (name "unconnected-(CON1-JTAG-Pad6)") (class "Default")
      (node (ref "CON1") (pin "6") (pinfunction "JTAG_6") (pintype "passive"))
    )
    (net (code "231") (name "unconnected-(CON1-JTAG-Pad8)") (class "Default")
      (node (ref "CON1") (pin "8") (pinfunction "JTAG_8") (pintype "passive"))
    )
    (net (code "232") (name "unconnected-(CON1-JTAG-Pad10)") (class "Default")
      (node (ref "CON1") (pin "10") (pinfunction "JTAG_10") (pintype "passive"))
    )
    (net (code "233") (name "unconnected-(CON1-JTAG-Pad12)") (class "Default")
      (node (ref "CON1") (pin "12") (pinfunction "JTAG_12") (pintype "passive"))
    )
    (net (code "234") (name "unconnected-(CON1-JTAG-Pad14)") (class "Default")
      (node (ref "CON1") (pin "14") (pinfunction "JTAG_14") (pintype "passive"))
    )
    (net (code "235") (name "unconnected-(CON1-Pad5)") (class "Default")
      (node (ref "CON1") (pin "5") (pinfunction "5_5") (pintype "passive"))
    )
    (net (code "236") (name "unconnected-(CON1-VDD_13-Pad15)") (class "Default")
      (node (ref "CON1") (pin "15") (pinfunction "VDD_13_15") (pintype "passive"))
    )
    (net (code "237") (name "unconnected-(CON1-VDD_34-Pad49)") (class "Default")
      (node (ref "CON1") (pin "49") (pinfunction "VDD_34_49") (pintype "passive"))
    )
    (net (code "238") (name "unconnected-(CON2-ADC-Pad5)") (class "Default")
      (node (ref "CON2") (pin "5") (pinfunction "ADC_5") (pintype "passive"))
    )
    (net (code "239") (name "unconnected-(CON2-ADC-Pad7)") (class "Default")
      (node (ref "CON2") (pin "7") (pinfunction "ADC_7") (pintype "passive"))
    )
    (net (code "240") (name "unconnected-(CON2-ADC_VCC-Pad9)") (class "Default")
      (node (ref "CON2") (pin "9") (pinfunction "ADC_VCC_9") (pintype "passive"))
    )
    (net (code "241") (name "unconnected-(CON2-CAN_RX-Pad16)") (class "Default")
      (node (ref "CON2") (pin "16") (pinfunction "CAN_RX_16") (pintype "passive"))
    )
    (net (code "242") (name "unconnected-(CON2-CAN_TX-Pad18)") (class "Default")
      (node (ref "CON2") (pin "18") (pinfunction "CAN_TX_18") (pintype "passive"))
    )
    (net (code "243") (name "unconnected-(CON2-CLK-Pad17)") (class "Default")
      (node (ref "CON2") (pin "17") (pinfunction "CLK_17") (pintype "passive"))
    )
    (net (code "244") (name "unconnected-(CON2-DN-Pad8)") (class "Default")
      (node (ref "CON2") (pin "8") (pinfunction "DN_8") (pintype "passive"))
    )
    (net (code "245") (name "unconnected-(CON2-DP-Pad6)") (class "Default")
      (node (ref "CON2") (pin "6") (pinfunction "DP_6") (pintype "passive"))
    )
    (net (code "246") (name "unconnected-(CON2-NAND-Pad13)") (class "Default")
      (node (ref "CON2") (pin "13") (pinfunction "NAND_13") (pintype "passive"))
    )
    (net (code "247") (name "unconnected-(CON2-PS_LED-Pad11)") (class "Default")
      (node (ref "CON2") (pin "11") (pinfunction "PS_LED_11") (pintype "passive"))
    )
    (net (code "248") (name "unconnected-(CON2-PS_LED-Pad15)") (class "Default")
      (node (ref "CON2") (pin "15") (pinfunction "PS_LED_15") (pintype "passive"))
    )
    (net (code "249") (name "unconnected-(CON2-SDA-Pad19)") (class "Default")
      (node (ref "CON2") (pin "19") (pinfunction "SDA_19") (pintype "passive"))
    )
    (net (code "250") (name "unconnected-(CON2-UART_RX-Pad12)") (class "Default")
      (node (ref "CON2") (pin "12") (pinfunction "UART_RX_12") (pintype "passive"))
    )
    (net (code "251") (name "unconnected-(CON2-UART_TX-Pad14)") (class "Default")
      (node (ref "CON2") (pin "14") (pinfunction "UART_TX_14") (pintype "passive"))
    )
    (net (code "252") (name "unconnected-(P1-Pad3)") (class "Default")
      (node (ref "P1") (pin "3") (pinfunction "3_3") (pintype "passive"))
    )
    (net (code "253") (name "unconnected-(P2-Pad3)") (class "Default")
      (node (ref "P2") (pin "3") (pinfunction "3_3") (pintype "passive"))
    )
    (net (code "254") (name "unconnected-(P3-Pad3)") (class "Default")
      (node (ref "P3") (pin "3") (pinfunction "3_3") (pintype "passive"))
    )
    (net (code "255") (name "unconnected-(P4-Pad3)") (class "Default")
      (node (ref "P4") (pin "3") (pinfunction "3_3") (pintype "passive"))
    )
    (net (code "256") (name "unconnected-(P5-Pad3)") (class "Default")
      (node (ref "P5") (pin "3") (pinfunction "3_3") (pintype "passive"))
    )
    (net (code "257") (name "unconnected-(U25-EN-Pad4)") (class "Default")
      (node (ref "U25") (pin "4") (pinfunction "EN_4") (pintype "input"))
    )
    (net (code "258") (name "unconnected-(U25-NC-Pad9)") (class "Default")
      (node (ref "U25") (pin "9") (pinfunction "NC_9") (pintype "passive"))
    )
    (net (code "259") (name "unconnected-(U26-EN-Pad3)") (class "Default")
      (node (ref "U26") (pin "3") (pinfunction "EN_3") (pintype "input"))
    )
  )
)
